# Down_Linker_ver1_0_0.net
KiCad netlist of a schematic drawn in EAGLE
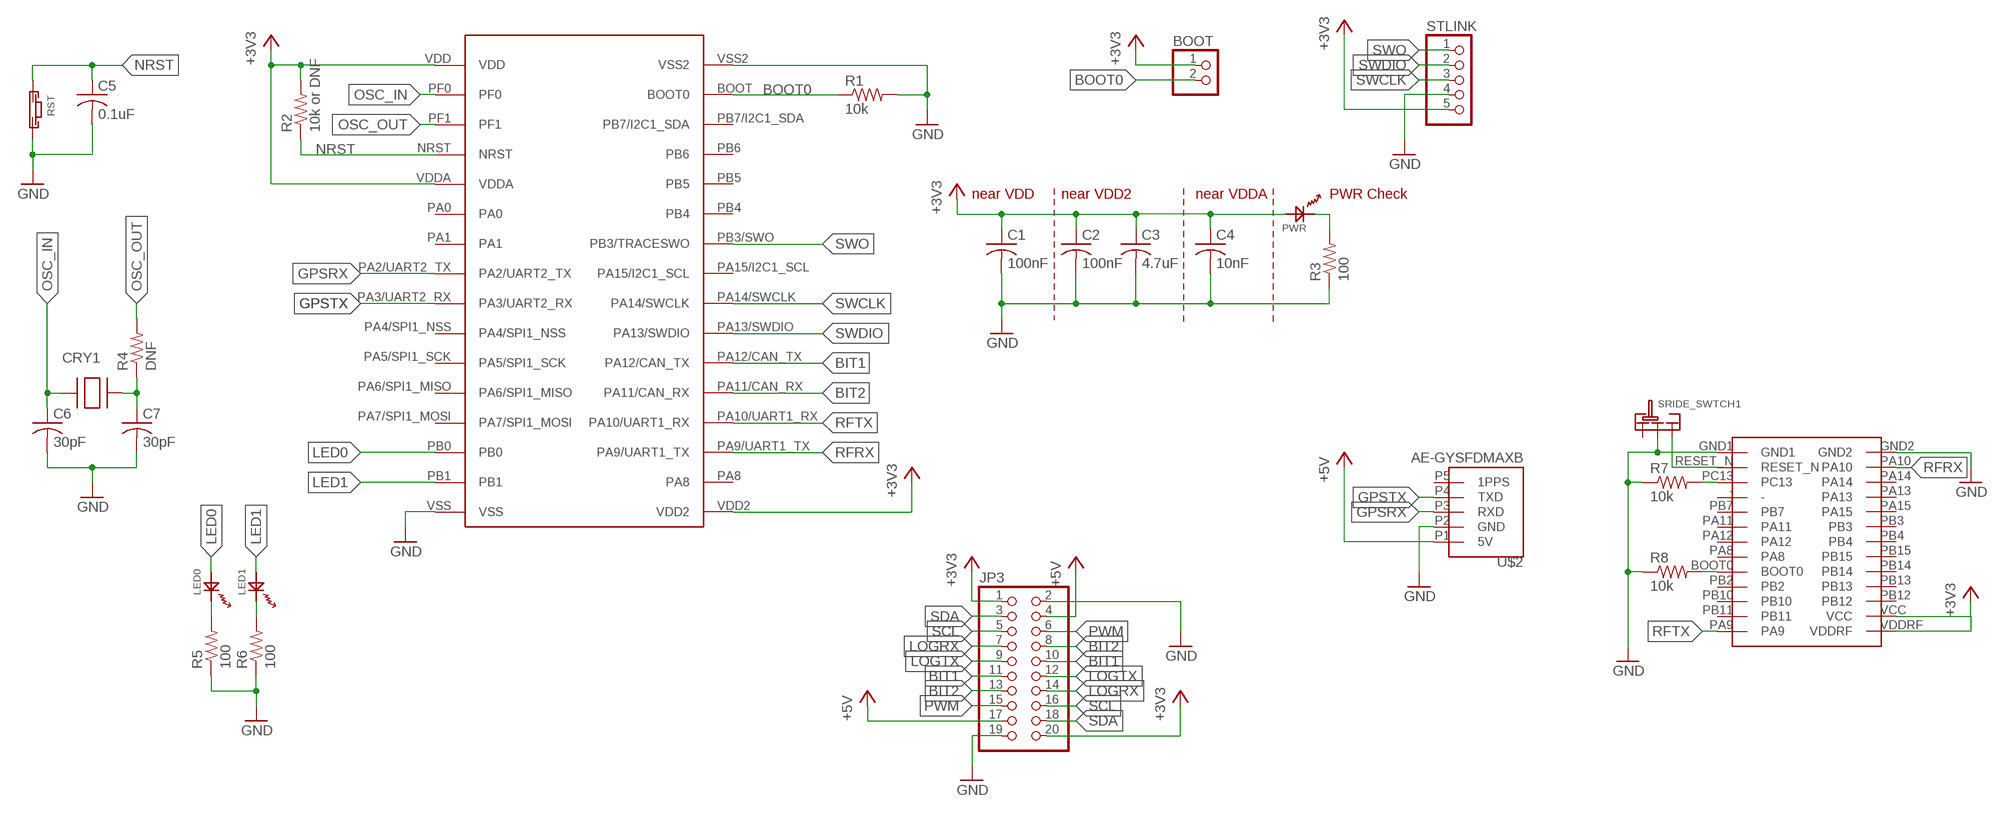
[diagram p0: schematic, sheet 1]

(export (version "E")
  (design (tool "Eeschema 10.0.6"))
  (components
    (comp (ref "BOOT")
      (value "PINHD-1X2/90")
      (footprint "eagle-import:1X02_90")
      (libsource (lib "eagle-import") (part "PINHD-1X2/90"))
    )
    (comp (ref "C1")
      (value "100nF")
      (footprint "eagle-import:C1608")
      (libsource (lib "eagle-import") (part "C-USC1608"))
    )
    (comp (ref "C2")
      (value "100nF")
      (footprint "eagle-import:C1608")
      (libsource (lib "eagle-import") (part "C-USC1608"))
    )
    (comp (ref "C3")
      (value "4.7uF")
      (footprint "eagle-import:C1608")
      (libsource (lib "eagle-import") (part "C-USC1608"))
    )
    (comp (ref "C4")
      (value "10nF")
      (footprint "eagle-import:C1608")
      (libsource (lib "eagle-import") (part "C-USC1608"))
    )
    (comp (ref "C5")
      (value "0.1uF")
      (footprint "eagle-import:C1608")
      (libsource (lib "eagle-import") (part "C-USC1608"))
    )
    (comp (ref "C6")
      (value "30pF")
      (footprint "eagle-import:C1608")
      (libsource (lib "eagle-import") (part "C-USC1608"))
    )
    (comp (ref "C7")
      (value "30pF")
      (footprint "eagle-import:C1608")
      (libsource (lib "eagle-import") (part "C-USC1608"))
    )
    (comp (ref "CRY1")
      (value "8MHZ")
      (footprint "eagle-import:CRYSTAL")
      (libsource (lib "eagle-import") (part "8MHZ"))
    )
    (comp (ref "JP3")
      (value "PINHD-2X10/90")
      (footprint "eagle-import:2X10_90")
      (libsource (lib "eagle-import") (part "PINHD-2X10/90"))
    )
    (comp (ref "LED0")
      (value "OSXX1608C1A")
      (footprint "eagle-import:OSXX1608C1A")
      (libsource (lib "eagle-import") (part "OSXX1608C1A"))
    )
    (comp (ref "LED1")
      (value "OSXX1608C1A")
      (footprint "eagle-import:OSXX1608C1A")
      (libsource (lib "eagle-import") (part "OSXX1608C1A"))
    )
    (comp (ref "PWR")
      (value "OSXX1608C1A")
      (footprint "eagle-import:OSXX1608C1A")
      (libsource (lib "eagle-import") (part "OSXX1608C1A"))
    )
    (comp (ref "R1")
      (value "10k")
      (footprint "eagle-import:R0603")
      (libsource (lib "eagle-import") (part "R-US_R0603"))
    )
    (comp (ref "R2")
      (value "10k or DNF")
      (footprint "eagle-import:R0603")
      (libsource (lib "eagle-import") (part "R-US_R0603"))
    )
    (comp (ref "R3")
      (value "100")
      (footprint "eagle-import:R0603")
      (libsource (lib "eagle-import") (part "R-US_R0603"))
    )
    (comp (ref "R4")
      (value "DNF")
      (footprint "eagle-import:R0603")
      (libsource (lib "eagle-import") (part "R-US_R0603"))
    )
    (comp (ref "R5")
      (value "100")
      (footprint "eagle-import:R0603")
      (libsource (lib "eagle-import") (part "R-US_R0603"))
    )
    (comp (ref "R6")
      (value "100")
      (footprint "eagle-import:R0603")
      (libsource (lib "eagle-import") (part "R-US_R0603"))
    )
    (comp (ref "R7")
      (value "10k")
      (footprint "eagle-import:R0603")
      (libsource (lib "eagle-import") (part "R-US_R0603"))
    )
    (comp (ref "R8")
      (value "10k")
      (footprint "eagle-import:R0603")
      (libsource (lib "eagle-import") (part "R-US_R0603"))
    )
    (comp (ref "RST")
      (value "TVAF06-A020B-R")
      (footprint "eagle-import:TVAF06-A020B-R")
      (libsource (lib "eagle-import") (part "TVAF06-A020B-R"))
    )
    (comp (ref "SRIDE_SWTCH1")
      (value "SRIDE_SWITCH")
      (footprint "eagle-import:SRIDE_SWITCH")
      (libsource (lib "eagle-import") (part "SRIDE_SWITCH"))
    )
    (comp (ref "STLINK")
      (value "PINHD-1X5/90")
      (footprint "eagle-import:1X05_90")
      (libsource (lib "eagle-import") (part "PINHD-1X5/90"))
    )
    (comp (ref "U$1")
      (value "STM32F303K8")
      (footprint "eagle-import:STM32F303K8")
      (libsource (lib "eagle-import") (part "STM32F303K8"))
    )
    (comp (ref "U$2")
      (value "AE-GYSFDMAXB")
      (footprint "eagle-import:AE-GYSFDMAXB")
      (libsource (lib "eagle-import") (part "AE-GYSFDMAXB"))
    )
    (comp (ref "U$3")
      (value "RM-92A")
      (footprint "eagle-import:RM-92A")
      (libsource (lib "eagle-import") (part "RM-92A"))
    )
  )
  (nets
    (net (code "1") (name "+3V3") (class "Default")
      (node (ref "BOOT") (pin "1") (pinfunction "1_1") (pintype "passive"))
      (node (ref "C1") (pin "1") (pinfunction "1_1") (pintype "passive"))
      (node (ref "C2") (pin "1") (pinfunction "1_1") (pintype "passive"))
      (node (ref "C3") (pin "1") (pinfunction "1_1") (pintype "passive"))
      (node (ref "C4") (pin "1") (pinfunction "1_1") (pintype "passive"))
      (node (ref "JP3") (pin "1") (pinfunction "1_1") (pintype "passive"))
      (node (ref "JP3") (pin "20") (pinfunction "20_20") (pintype "passive"))
      (node (ref "PWR") (pin "AN") (pinfunction "AN_AN") (pintype "bidirectional"))
      (node (ref "R2") (pin "2") (pinfunction "2_2") (pintype "passive"))
      (node (ref "STLINK") (pin "5") (pinfunction "5_5") (pintype "passive"))
      (node (ref "U$1") (pin "VDD") (pinfunction "VDD_VDD") (pintype "power_in"))
      (node (ref "U$1") (pin "VDD2") (pinfunction "VDD2_VDD2") (pintype "power_in"))
      (node (ref "U$1") (pin "VDDA") (pinfunction "VDDA_VDDA") (pintype "power_in"))
      (node (ref "U$3") (pin "VCC") (pinfunction "VCC_VCC") (pintype "bidirectional"))
      (node (ref "U$3") (pin "VDDRF") (pinfunction "VDDRF_VDDRF") (pintype "bidirectional"))
    )
    (net (code "2") (name "+5V") (class "Default")
      (node (ref "JP3") (pin "17") (pinfunction "17_17") (pintype "passive"))
      (node (ref "JP3") (pin "4") (pinfunction "4_4") (pintype "passive"))
      (node (ref "U$2") (pin "P1") (pinfunction "5V_P1") (pintype "bidirectional"))
    )
    (net (code "3") (name "BIT1") (class "Default")
      (node (ref "JP3") (pin "10") (pinfunction "10_10") (pintype "passive"))
      (node (ref "JP3") (pin "11") (pinfunction "11_11") (pintype "passive"))
      (node (ref "U$1") (pin "PA12/CAN_TX") (pinfunction "PA12/CAN_TX_PA12/CAN_TX") (pintype "bidirectional"))
    )
    (net (code "4") (name "BIT2") (class "Default")
      (node (ref "JP3") (pin "13") (pinfunction "13_13") (pintype "passive"))
      (node (ref "JP3") (pin "8") (pinfunction "8_8") (pintype "passive"))
      (node (ref "U$1") (pin "PA11/CAN_RX") (pinfunction "PA11/CAN_RX_PA11/CAN_RX") (pintype "bidirectional"))
    )
    (net (code "5") (name "BOOT0") (class "Default")
      (node (ref "BOOT") (pin "2") (pinfunction "2_2") (pintype "passive"))
      (node (ref "R1") (pin "1") (pinfunction "1_1") (pintype "passive"))
      (node (ref "U$1") (pin "BOOT") (pinfunction "BOOT0_BOOT") (pintype "bidirectional"))
    )
    (net (code "6") (name "GND") (class "Default")
      (node (ref "C1") (pin "2") (pinfunction "2_2") (pintype "passive"))
      (node (ref "C2") (pin "2") (pinfunction "2_2") (pintype "passive"))
      (node (ref "C3") (pin "2") (pinfunction "2_2") (pintype "passive"))
      (node (ref "C4") (pin "2") (pinfunction "2_2") (pintype "passive"))
      (node (ref "C5") (pin "2") (pinfunction "2_2") (pintype "passive"))
      (node (ref "C6") (pin "2") (pinfunction "2_2") (pintype "passive"))
      (node (ref "C7") (pin "2") (pinfunction "2_2") (pintype "passive"))
      (node (ref "JP3") (pin "19") (pinfunction "19_19") (pintype "passive"))
      (node (ref "JP3") (pin "2") (pinfunction "2_2") (pintype "passive"))
      (node (ref "R1") (pin "2") (pinfunction "2_2") (pintype "passive"))
      (node (ref "R3") (pin "1") (pinfunction "1_1") (pintype "passive"))
      (node (ref "R5") (pin "1") (pinfunction "1_1") (pintype "passive"))
      (node (ref "R6") (pin "1") (pinfunction "1_1") (pintype "passive"))
      (node (ref "R7") (pin "1") (pinfunction "1_1") (pintype "passive"))
      (node (ref "R8") (pin "1") (pinfunction "1_1") (pintype "passive"))
      (node (ref "RST") (pin "P$2") (pinfunction "P$2_P$2") (pintype "bidirectional"))
      (node (ref "SRIDE_SWTCH1") (pin "LR") (pinfunction "LR_LR") (pintype "bidirectional"))
      (node (ref "STLINK") (pin "4") (pinfunction "4_4") (pintype "passive"))
      (node (ref "U$1") (pin "VSS") (pinfunction "VSS_VSS") (pintype "power_in"))
      (node (ref "U$1") (pin "VSS2") (pinfunction "VSS2_VSS2") (pintype "power_in"))
      (node (ref "U$2") (pin "P2") (pinfunction "GND_P2") (pintype "bidirectional"))
      (node (ref "U$3") (pin "GND1") (pinfunction "GND1_GND1") (pintype "bidirectional"))
      (node (ref "U$3") (pin "GND2") (pinfunction "GND2_GND2") (pintype "bidirectional"))
    )
    (net (code "7") (name "GPSRX") (class "Default")
      (node (ref "U$1") (pin "PA2/UART2_TX") (pinfunction "PA2/UART2_TX_PA2/UART2_TX") (pintype "bidirectional"))
      (node (ref "U$2") (pin "P3") (pinfunction "RXD_P3") (pintype "bidirectional"))
    )
    (net (code "8") (name "GPSTX") (class "Default")
      (node (ref "U$1") (pin "PA3/UART2_RX") (pinfunction "PA3/UART2_RX_PA3/UART2_RX") (pintype "bidirectional"))
      (node (ref "U$2") (pin "P4") (pinfunction "TXD_P4") (pintype "bidirectional"))
    )
    (net (code "9") (name "LED0") (class "Default")
      (node (ref "LED0") (pin "AN") (pinfunction "AN_AN") (pintype "bidirectional"))
      (node (ref "U$1") (pin "PB0") (pinfunction "PB0_PB0") (pintype "bidirectional"))
    )
    (net (code "10") (name "LED1") (class "Default")
      (node (ref "LED1") (pin "AN") (pinfunction "AN_AN") (pintype "bidirectional"))
      (node (ref "U$1") (pin "PB1") (pinfunction "PB1_PB1") (pintype "bidirectional"))
    )
    (net (code "11") (name "LOGRX") (class "Default")
      (node (ref "JP3") (pin "14") (pinfunction "14_14") (pintype "passive"))
      (node (ref "JP3") (pin "7") (pinfunction "7_7") (pintype "passive"))
    )
    (net (code "12") (name "LOGTX") (class "Default")
      (node (ref "JP3") (pin "12") (pinfunction "12_12") (pintype "passive"))
      (node (ref "JP3") (pin "9") (pinfunction "9_9") (pintype "passive"))
    )
    (net (code "13") (name "NRST") (class "Default")
      (node (ref "C5") (pin "1") (pinfunction "1_1") (pintype "passive"))
      (node (ref "R2") (pin "1") (pinfunction "1_1") (pintype "passive"))
      (node (ref "RST") (pin "P$1") (pinfunction "P$1_P$1") (pintype "bidirectional"))
      (node (ref "U$1") (pin "NRST") (pinfunction "NRST_NRST") (pintype "bidirectional"))
    )
    (net (code "14") (name "Net-(C7-Pad1)") (class "Default")
      (node (ref "C7") (pin "1") (pinfunction "1_1") (pintype "passive"))
      (node (ref "CRY1") (pin "P$2") (pinfunction "P$2_P$2") (pintype "bidirectional"))
      (node (ref "R4") (pin "1") (pinfunction "1_1") (pintype "passive"))
    )
    (net (code "15") (name "Net-(LED0-PadCT)") (class "Default")
      (node (ref "LED0") (pin "CT") (pinfunction "CT_CT") (pintype "bidirectional"))
      (node (ref "R5") (pin "2") (pinfunction "2_2") (pintype "passive"))
    )
    (net (code "16") (name "Net-(LED1-PadCT)") (class "Default")
      (node (ref "LED1") (pin "CT") (pinfunction "CT_CT") (pintype "bidirectional"))
      (node (ref "R6") (pin "2") (pinfunction "2_2") (pintype "passive"))
    )
    (net (code "17") (name "Net-(PWR-PadCT)") (class "Default")
      (node (ref "PWR") (pin "CT") (pinfunction "CT_CT") (pintype "bidirectional"))
      (node (ref "R3") (pin "2") (pinfunction "2_2") (pintype "passive"))
    )
    (net (code "18") (name "Net-(R7-Pad2)") (class "Default")
      (node (ref "R7") (pin "2") (pinfunction "2_2") (pintype "passive"))
      (node (ref "U$3") (pin "PC13") (pinfunction "PC13_PC13") (pintype "bidirectional"))
    )
    (net (code "19") (name "Net-(R8-Pad2)") (class "Default")
      (node (ref "R8") (pin "2") (pinfunction "2_2") (pintype "passive"))
      (node (ref "U$3") (pin "BOOT0") (pinfunction "BOOT0_BOOT0") (pintype "bidirectional"))
    )
    (net (code "20") (name "Net-(SRIDE_SWTCH1-PadR)") (class "Default")
      (node (ref "SRIDE_SWTCH1") (pin "R") (pinfunction "R_R") (pintype "bidirectional"))
      (node (ref "U$3") (pin "RESET_N") (pinfunction "RESET_N_RESET_N") (pintype "bidirectional"))
    )
    (net (code "21") (name "OSC_IN") (class "Default")
      (node (ref "C6") (pin "1") (pinfunction "1_1") (pintype "passive"))
      (node (ref "CRY1") (pin "P$1") (pinfunction "P$1_P$1") (pintype "bidirectional"))
      (node (ref "U$1") (pin "PF0") (pinfunction "PF0_PF0") (pintype "bidirectional"))
    )
    (net (code "22") (name "OSC_OUT") (class "Default")
      (node (ref "R4") (pin "2") (pinfunction "2_2") (pintype "passive"))
      (node (ref "U$1") (pin "PF1") (pinfunction "PF1_PF1") (pintype "bidirectional"))
    )
    (net (code "23") (name "PWM") (class "Default")
      (node (ref "JP3") (pin "15") (pinfunction "15_15") (pintype "passive"))
      (node (ref "JP3") (pin "6") (pinfunction "6_6") (pintype "passive"))
    )
    (net (code "24") (name "RFRX") (class "Default")
      (node (ref "U$1") (pin "PA9/UART1_TX") (pinfunction "PA9/UART1_TX_PA9/UART1_TX") (pintype "bidirectional"))
      (node (ref "U$3") (pin "PA10") (pinfunction "PA10_PA10") (pintype "bidirectional"))
    )
    (net (code "25") (name "RFTX") (class "Default")
      (node (ref "U$1") (pin "PA10/UART1_RX") (pinfunction "PA10/UART1_RX_PA10/UART1_RX") (pintype "bidirectional"))
      (node (ref "U$3") (pin "PA9") (pinfunction "PA9_PA9") (pintype "bidirectional"))
    )
    (net (code "26") (name "SCL") (class "Default")
      (node (ref "JP3") (pin "16") (pinfunction "16_16") (pintype "passive"))
      (node (ref "JP3") (pin "5") (pinfunction "5_5") (pintype "passive"))
    )
    (net (code "27") (name "SDA") (class "Default")
      (node (ref "JP3") (pin "18") (pinfunction "18_18") (pintype "passive"))
      (node (ref "JP3") (pin "3") (pinfunction "3_3") (pintype "passive"))
    )
    (net (code "28") (name "SWCLK") (class "Default")
      (node (ref "STLINK") (pin "3") (pinfunction "3_3") (pintype "passive"))
      (node (ref "U$1") (pin "PA14/SWCLK") (pinfunction "PA14/SWCLK_PA14/SWCLK") (pintype "bidirectional"))
    )
    (net (code "29") (name "SWDIO") (class "Default")
      (node (ref "STLINK") (pin "2") (pinfunction "2_2") (pintype "passive"))
      (node (ref "U$1") (pin "PA13/SWDIO") (pinfunction "PA13/SWDIO_PA13/SWDIO") (pintype "bidirectional"))
    )
    (net (code "30") (name "SWO") (class "Default")
      (node (ref "STLINK") (pin "1") (pinfunction "1_1") (pintype "passive"))
      (node (ref "U$1") (pin "PB3/SWO") (pinfunction "PB3/TRACESWO_PB3/SWO") (pintype "bidirectional"))
    )
    (net (code "31") (name "unconnected-(SRIDE_SWTCH1-PadL)") (class "Default")
      (node (ref "SRIDE_SWTCH1") (pin "L") (pinfunction "L_L") (pintype "bidirectional"))
    )
    (net (code "32") (name "unconnected-(U$1-PadPA0)") (class "Default")
      (node (ref "U$1") (pin "PA0") (pinfunction "PA0_PA0") (pintype "bidirectional"))
    )
    (net (code "33") (name "unconnected-(U$1-PadPA1)") (class "Default")
      (node (ref "U$1") (pin "PA1") (pinfunction "PA1_PA1") (pintype "bidirectional"))
    )
    (net (code "34") (name "unconnected-(U$1-PadPA4{slash}SPI1_NSS)") (class "Default")
      (node (ref "U$1") (pin "PA4/SPI1_NSS") (pinfunction "PA4/SPI1_NSS_PA4/SPI1_NSS") (pintype "bidirectional"))
    )
    (net (code "35") (name "unconnected-(U$1-PadPA5{slash}SPI1_SCK)") (class "Default")
      (node (ref "U$1") (pin "PA5/SPI1_SCK") (pinfunction "PA5/SPI1_SCK_PA5/SPI1_SCK") (pintype "bidirectional"))
    )
    (net (code "36") (name "unconnected-(U$1-PadPA6{slash}SPI1_MISO)") (class "Default")
      (node (ref "U$1") (pin "PA6/SPI1_MISO") (pinfunction "PA6/SPI1_MISO_PA6/SPI1_MISO") (pintype "bidirectional"))
    )
    (net (code "37") (name "unconnected-(U$1-PadPA7{slash}SPI1_MOSI)") (class "Default")
      (node (ref "U$1") (pin "PA7/SPI1_MOSI") (pinfunction "PA7/SPI1_MOSI_PA7/SPI1_MOSI") (pintype "bidirectional"))
    )
    (net (code "38") (name "unconnected-(U$1-PadPA8)") (class "Default")
      (node (ref "U$1") (pin "PA8") (pinfunction "PA8_PA8") (pintype "bidirectional"))
    )
    (net (code "39") (name "unconnected-(U$1-PadPA15{slash}I2C1_SCL)") (class "Default")
      (node (ref "U$1") (pin "PA15/I2C1_SCL") (pinfunction "PA15/I2C1_SCL_PA15/I2C1_SCL") (pintype "bidirectional"))
    )
    (net (code "40") (name "unconnected-(U$1-PadPB4)") (class "Default")
      (node (ref "U$1") (pin "PB4") (pinfunction "PB4_PB4") (pintype "bidirectional"))
    )
    (net (code "41") (name "unconnected-(U$1-PadPB5)") (class "Default")
      (node (ref "U$1") (pin "PB5") (pinfunction "PB5_PB5") (pintype "bidirectional"))
    )
    (net (code "42") (name "unconnected-(U$1-PadPB6)") (class "Default")
      (node (ref "U$1") (pin "PB6") (pinfunction "PB6_PB6") (pintype "bidirectional"))
    )
    (net (code "43") (name "unconnected-(U$1-PadPB7{slash}I2C1_SDA)") (class "Default")
      (node (ref "U$1") (pin "PB7/I2C1_SDA") (pinfunction "PB7/I2C1_SDA_PB7/I2C1_SDA") (pintype "bidirectional"))
    )
    (net (code "44") (name "unconnected-(U$2-1PPS-PadP5)") (class "Default")
      (node (ref "U$2") (pin "P5") (pinfunction "1PPS_P5") (pintype "bidirectional"))
    )
    (net (code "45") (name "unconnected-(U$3-Pad-)") (class "Default")
      (node (ref "U$3") (pin "-") (pinfunction "-_-") (pintype "bidirectional"))
    )
    (net (code "46") (name "unconnected-(U$3-PadPA8)") (class "Default")
      (node (ref "U$3") (pin "PA8") (pinfunction "PA8_PA8") (pintype "bidirectional"))
    )
    (net (code "47") (name "unconnected-(U$3-PadPA11)") (class "Default")
      (node (ref "U$3") (pin "PA11") (pinfunction "PA11_PA11") (pintype "bidirectional"))
    )
    (net (code "48") (name "unconnected-(U$3-PadPA12)") (class "Default")
      (node (ref "U$3") (pin "PA12") (pinfunction "PA12_PA12") (pintype "bidirectional"))
    )
    (net (code "49") (name "unconnected-(U$3-PadPA13)") (class "Default")
      (node (ref "U$3") (pin "PA13") (pinfunction "PA13_PA13") (pintype "bidirectional"))
    )
    (net (code "50") (name "unconnected-(U$3-PadPA14)") (class "Default")
      (node (ref "U$3") (pin "PA14") (pinfunction "PA14_PA14") (pintype "bidirectional"))
    )
    (net (code "51") (name "unconnected-(U$3-PadPA15)") (class "Default")
      (node (ref "U$3") (pin "PA15") (pinfunction "PA15_PA15") (pintype "bidirectional"))
    )
    (net (code "52") (name "unconnected-(U$3-PadPB2)") (class "Default")
      (node (ref "U$3") (pin "PB2") (pinfunction "PB2_PB2") (pintype "bidirectional"))
    )
    (net (code "53") (name "unconnected-(U$3-PadPB3)") (class "Default")
      (node (ref "U$3") (pin "PB3") (pinfunction "PB3_PB3") (pintype "bidirectional"))
    )
    (net (code "54") (name "unconnected-(U$3-PadPB4)") (class "Default")
      (node (ref "U$3") (pin "PB4") (pinfunction "PB4_PB4") (pintype "bidirectional"))
    )
    (net (code "55") (name "unconnected-(U$3-PadPB7)") (class "Default")
      (node (ref "U$3") (pin "PB7") (pinfunction "PB7_PB7") (pintype "bidirectional"))
    )
    (net (code "56") (name "unconnected-(U$3-PadPB10)") (class "Default")
      (node (ref "U$3") (pin "PB10") (pinfunction "PB10_PB10") (pintype "bidirectional"))
    )
    (net (code "57") (name "unconnected-(U$3-PadPB11)") (class "Default")
      (node (ref "U$3") (pin "PB11") (pinfunction "PB11_PB11") (pintype "bidirectional"))
    )
    (net (code "58") (name "unconnected-(U$3-PadPB12)") (class "Default")
      (node (ref "U$3") (pin "PB12") (pinfunction "PB12_PB12") (pintype "bidirectional"))
    )
    (net (code "59") (name "unconnected-(U$3-PadPB13)") (class "Default")
      (node (ref "U$3") (pin "PB13") (pinfunction "PB13_PB13") (pintype "bidirectional"))
    )
    (net (code "60") (name "unconnected-(U$3-PadPB14)") (class "Default")
      (node (ref "U$3") (pin "PB14") (pinfunction "PB14_PB14") (pintype "bidirectional"))
    )
    (net (code "61") (name "unconnected-(U$3-PadPB15)") (class "Default")
      (node (ref "U$3") (pin "PB15") (pinfunction "PB15_PB15") (pintype "bidirectional"))
    )
  )
)
